# openhum2.net
KiCad netlist of a schematic drawn in EAGLE
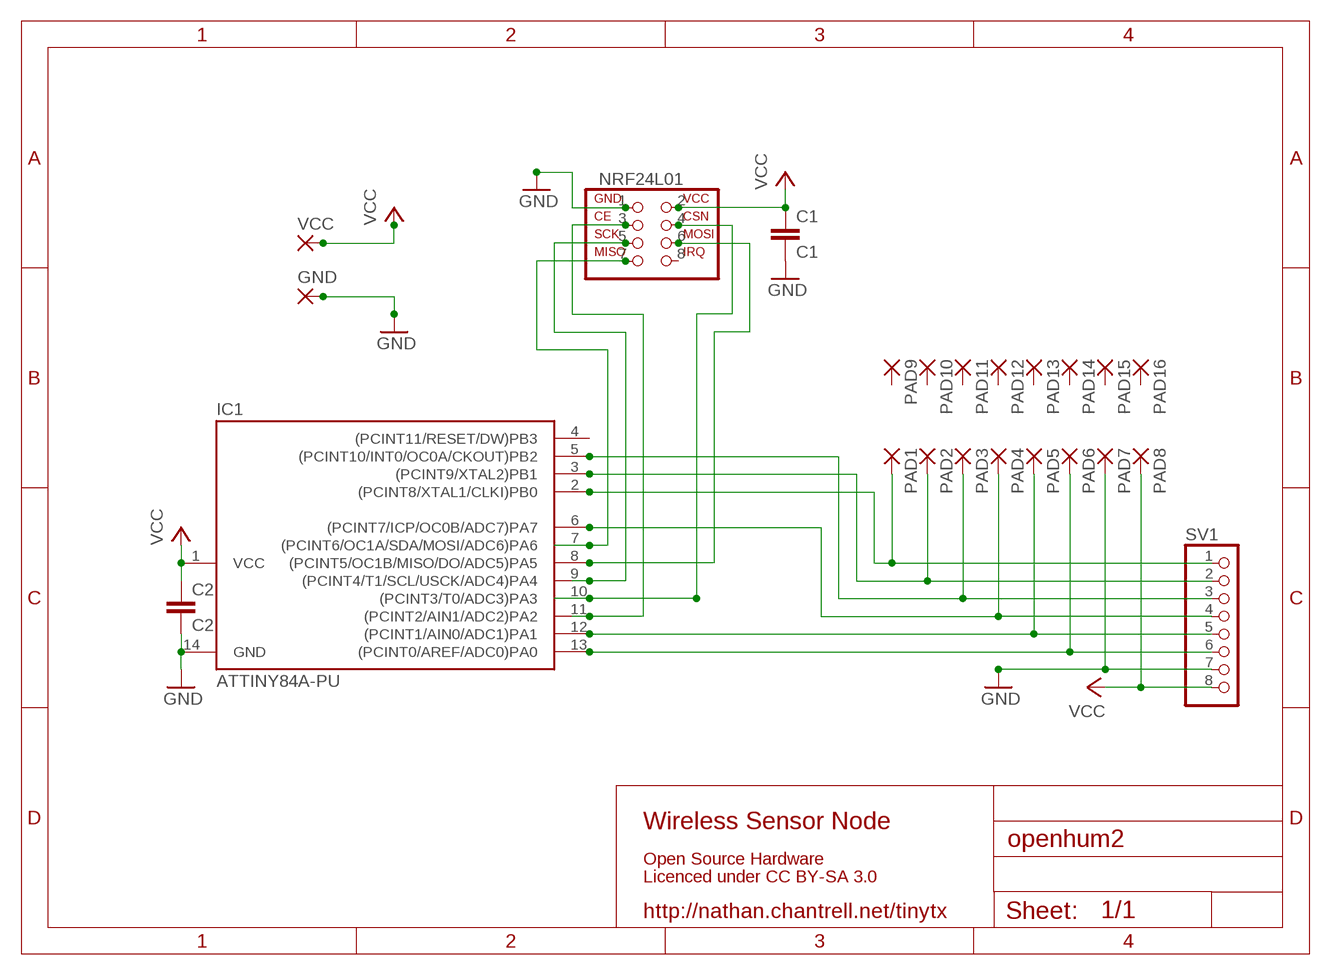
[diagram p0: schematic, sheet 1]

(export (version "E")
  (design (tool "Eeschema 10.0.6"))
  (components
    (comp (ref "C1")
      (value "C1")
      (footprint "eagle-import:C025-025X050")
      (libsource (lib "eagle-import") (part "C-EU025-025X050"))
    )
    (comp (ref "C2")
      (value "C2")
      (footprint "eagle-import:C025-025X050")
      (libsource (lib "eagle-import") (part "C-EU025-025X050"))
    )
    (comp (ref "GND")
      (value "2,15/1,0")
      (footprint "eagle-import:2,15_1,0")
      (libsource (lib "eagle-import") (part "2,15/1,0"))
    )
    (comp (ref "IC1")
      (value "ATTINY84A-PU")
      (footprint "eagle-import:DIL14")
      (libsource (lib "eagle-import") (part "TINY24/44/84-PU"))
    )
    (comp (ref "NRF24L01")
      (value "NRF24L01+")
      (footprint "eagle-import:NRF24L01+")
      (libsource (lib "eagle-import") (part "NRF24L01+"))
    )
    (comp (ref "PAD1")
      (value "1,6/0,9")
      (footprint "eagle-import:1,6_0,9")
      (libsource (lib "eagle-import") (part "1,6/0,9"))
    )
    (comp (ref "PAD2")
      (value "1,6/0,9")
      (footprint "eagle-import:1,6_0,9")
      (libsource (lib "eagle-import") (part "1,6/0,9"))
    )
    (comp (ref "PAD3")
      (value "1,6/0,9")
      (footprint "eagle-import:1,6_0,9")
      (libsource (lib "eagle-import") (part "1,6/0,9"))
    )
    (comp (ref "PAD4")
      (value "1,6/0,9")
      (footprint "eagle-import:1,6_0,9")
      (libsource (lib "eagle-import") (part "1,6/0,9"))
    )
    (comp (ref "PAD5")
      (value "1,6/0,9")
      (footprint "eagle-import:1,6_0,9")
      (libsource (lib "eagle-import") (part "1,6/0,9"))
    )
    (comp (ref "PAD6")
      (value "1,6/0,9")
      (footprint "eagle-import:1,6_0,9")
      (libsource (lib "eagle-import") (part "1,6/0,9"))
    )
    (comp (ref "PAD7")
      (value "1,6/0,9")
      (footprint "eagle-import:1,6_0,9")
      (libsource (lib "eagle-import") (part "1,6/0,9"))
    )
    (comp (ref "PAD8")
      (value "1,6/0,9")
      (footprint "eagle-import:1,6_0,9")
      (libsource (lib "eagle-import") (part "1,6/0,9"))
    )
    (comp (ref "PAD9")
      (value "1,6/0,9")
      (footprint "eagle-import:1,6_0,9")
      (libsource (lib "eagle-import") (part "1,6/0,9"))
    )
    (comp (ref "PAD10")
      (value "1,6/0,9")
      (footprint "eagle-import:1,6_0,9")
      (libsource (lib "eagle-import") (part "1,6/0,9"))
    )
    (comp (ref "PAD11")
      (value "1,6/0,9")
      (footprint "eagle-import:1,6_0,9")
      (libsource (lib "eagle-import") (part "1,6/0,9"))
    )
    (comp (ref "PAD12")
      (value "1,6/0,9")
      (footprint "eagle-import:1,6_0,9")
      (libsource (lib "eagle-import") (part "1,6/0,9"))
    )
    (comp (ref "PAD13")
      (value "1,6/0,9")
      (footprint "eagle-import:1,6_0,9")
      (libsource (lib "eagle-import") (part "1,6/0,9"))
    )
    (comp (ref "PAD14")
      (value "1,6/0,9")
      (footprint "eagle-import:1,6_0,9")
      (libsource (lib "eagle-import") (part "1,6/0,9"))
    )
    (comp (ref "PAD15")
      (value "1,6/0,9")
      (footprint "eagle-import:1,6_0,9")
      (libsource (lib "eagle-import") (part "1,6/0,9"))
    )
    (comp (ref "PAD16")
      (value "1,6/0,9")
      (footprint "eagle-import:1,6_0,9")
      (libsource (lib "eagle-import") (part "1,6/0,9"))
    )
    (comp (ref "SV1")
      (value "PINHD-1X8")
      (footprint "eagle-import:1X08")
      (libsource (lib "eagle-import") (part "PINHD-1X8"))
    )
    (comp (ref "VCC")
      (value "2,15/1,0")
      (footprint "eagle-import:2,15_1,0")
      (libsource (lib "eagle-import") (part "2,15/1,0"))
    )
  )
  (nets
    (net (code "1") (name "GND") (class "Default")
      (node (ref "C1") (pin "2") (pinfunction "2_2") (pintype "passive"))
      (node (ref "C2") (pin "2") (pinfunction "2_2") (pintype "passive"))
      (node (ref "GND") (pin "1") (pinfunction "P_1") (pintype "passive"))
      (node (ref "IC1") (pin "14") (pinfunction "GND_14") (pintype "power_in"))
      (node (ref "NRF24L01") (pin "1") (pinfunction "1_1") (pintype "passive"))
      (node (ref "PAD7") (pin "1") (pinfunction "P_1") (pintype "passive"))
      (node (ref "SV1") (pin "7") (pinfunction "7_7") (pintype "passive"))
    )
    (net (code "2") (name "Net-(IC1-(PCINT0{slash}AREF{slash}ADC0)PA0)") (class "Default")
      (node (ref "IC1") (pin "13") (pinfunction "(PCINT0/AREF/ADC0)PA0_13") (pintype "bidirectional"))
      (node (ref "PAD6") (pin "1") (pinfunction "P_1") (pintype "passive"))
      (node (ref "SV1") (pin "6") (pinfunction "6_6") (pintype "passive"))
    )
    (net (code "3") (name "Net-(IC1-(PCINT1{slash}AIN0{slash}ADC1)PA1)") (class "Default")
      (node (ref "IC1") (pin "12") (pinfunction "(PCINT1/AIN0/ADC1)PA1_12") (pintype "bidirectional"))
      (node (ref "PAD5") (pin "1") (pinfunction "P_1") (pintype "passive"))
      (node (ref "SV1") (pin "5") (pinfunction "5_5") (pintype "passive"))
    )
    (net (code "4") (name "Net-(IC1-(PCINT2{slash}AIN1{slash}ADC2)PA2)") (class "Default")
      (node (ref "IC1") (pin "11") (pinfunction "(PCINT2/AIN1/ADC2)PA2_11") (pintype "bidirectional"))
      (node (ref "NRF24L01") (pin "3") (pinfunction "3_3") (pintype "passive"))
    )
    (net (code "5") (name "Net-(IC1-(PCINT3{slash}T0{slash}ADC3)PA3)") (class "Default")
      (node (ref "IC1") (pin "10") (pinfunction "(PCINT3/T0/ADC3)PA3_10") (pintype "bidirectional"))
      (node (ref "NRF24L01") (pin "4") (pinfunction "4_4") (pintype "passive"))
    )
    (net (code "6") (name "Net-(IC1-(PCINT4{slash}T1{slash}SCL{slash}USCK{slash}ADC4)PA4)") (class "Default")
      (node (ref "IC1") (pin "9") (pinfunction "(PCINT4/T1/SCL/USCK/ADC4)PA4_9") (pintype "bidirectional"))
      (node (ref "NRF24L01") (pin "5") (pinfunction "5_5") (pintype "passive"))
    )
    (net (code "7") (name "Net-(IC1-(PCINT5{slash}OC1B{slash}MISO{slash}DO{slash}ADC5)PA5)") (class "Default")
      (node (ref "IC1") (pin "8") (pinfunction "(PCINT5/OC1B/MISO/DO/ADC5)PA5_8") (pintype "bidirectional"))
      (node (ref "NRF24L01") (pin "6") (pinfunction "6_6") (pintype "passive"))
    )
    (net (code "8") (name "Net-(IC1-(PCINT6{slash}OC1A{slash}SDA{slash}MOSI{slash}ADC6)PA6)") (class "Default")
      (node (ref "IC1") (pin "7") (pinfunction "(PCINT6/OC1A/SDA/MOSI/ADC6)PA6_7") (pintype "bidirectional"))
      (node (ref "NRF24L01") (pin "7") (pinfunction "7_7") (pintype "passive"))
    )
    (net (code "9") (name "Net-(IC1-(PCINT7{slash}ICP{slash}OC0B{slash}ADC7)PA7)") (class "Default")
      (node (ref "IC1") (pin "6") (pinfunction "(PCINT7/ICP/OC0B/ADC7)PA7_6") (pintype "bidirectional"))
      (node (ref "PAD4") (pin "1") (pinfunction "P_1") (pintype "passive"))
      (node (ref "SV1") (pin "4") (pinfunction "4_4") (pintype "passive"))
    )
    (net (code "10") (name "Net-(IC1-(PCINT8{slash}XTAL1{slash}CLKI)PB0)") (class "Default")
      (node (ref "IC1") (pin "2") (pinfunction "(PCINT8/XTAL1/CLKI)PB0_2") (pintype "bidirectional"))
      (node (ref "PAD1") (pin "1") (pinfunction "P_1") (pintype "passive"))
      (node (ref "SV1") (pin "1") (pinfunction "1_1") (pintype "passive"))
    )
    (net (code "11") (name "Net-(IC1-(PCINT9{slash}XTAL2)PB1)") (class "Default")
      (node (ref "IC1") (pin "3") (pinfunction "(PCINT9/XTAL2)PB1_3") (pintype "bidirectional"))
      (node (ref "PAD2") (pin "1") (pinfunction "P_1") (pintype "passive"))
      (node (ref "SV1") (pin "2") (pinfunction "2_2") (pintype "passive"))
    )
    (net (code "12") (name "Net-(IC1-(PCINT10{slash}INT0{slash}OC0A{slash}CKOUT)PB2)") (class "Default")
      (node (ref "IC1") (pin "5") (pinfunction "(PCINT10/INT0/OC0A/CKOUT)PB2_5") (pintype "bidirectional"))
      (node (ref "PAD3") (pin "1") (pinfunction "P_1") (pintype "passive"))
      (node (ref "SV1") (pin "3") (pinfunction "3_3") (pintype "passive"))
    )
    (net (code "13") (name "VCC") (class "Default")
      (node (ref "C1") (pin "1") (pinfunction "1_1") (pintype "passive"))
      (node (ref "C2") (pin "1") (pinfunction "1_1") (pintype "passive"))
      (node (ref "IC1") (pin "1") (pinfunction "VCC_1") (pintype "power_in"))
      (node (ref "NRF24L01") (pin "2") (pinfunction "2_2") (pintype "passive"))
      (node (ref "PAD8") (pin "1") (pinfunction "P_1") (pintype "passive"))
      (node (ref "SV1") (pin "8") (pinfunction "8_8") (pintype "passive"))
      (node (ref "VCC") (pin "1") (pinfunction "P_1") (pintype "passive"))
    )
    (net (code "14") (name "unconnected-(IC1-(PCINT11{slash}RESET{slash}DW)PB3-Pad4)") (class "Default")
      (node (ref "IC1") (pin "4") (pinfunction "(PCINT11/RESET/DW)PB3_4") (pintype "bidirectional"))
    )
    (net (code "15") (name "unconnected-(NRF24L01-Pad8)") (class "Default")
      (node (ref "NRF24L01") (pin "8") (pinfunction "8_8") (pintype "passive"))
    )
    (net (code "16") (name "unconnected-(PAD9-P-Pad1)") (class "Default")
      (node (ref "PAD9") (pin "1") (pinfunction "P_1") (pintype "passive"))
    )
    (net (code "17") (name "unconnected-(PAD10-P-Pad1)") (class "Default")
      (node (ref "PAD10") (pin "1") (pinfunction "P_1") (pintype "passive"))
    )
    (net (code "18") (name "unconnected-(PAD11-P-Pad1)") (class "Default")
      (node (ref "PAD11") (pin "1") (pinfunction "P_1") (pintype "passive"))
    )
    (net (code "19") (name "unconnected-(PAD12-P-Pad1)") (class "Default")
      (node (ref "PAD12") (pin "1") (pinfunction "P_1") (pintype "passive"))
    )
    (net (code "20") (name "unconnected-(PAD13-P-Pad1)") (class "Default")
      (node (ref "PAD13") (pin "1") (pinfunction "P_1") (pintype "passive"))
    )
    (net (code "21") (name "unconnected-(PAD14-P-Pad1)") (class "Default")
      (node (ref "PAD14") (pin "1") (pinfunction "P_1") (pintype "passive"))
    )
    (net (code "22") (name "unconnected-(PAD15-P-Pad1)") (class "Default")
      (node (ref "PAD15") (pin "1") (pinfunction "P_1") (pintype "passive"))
    )
    (net (code "23") (name "unconnected-(PAD16-P-Pad1)") (class "Default")
      (node (ref "PAD16") (pin "1") (pinfunction "P_1") (pintype "passive"))
    )
  )
)
